# Easy_LED.net
KiCad netlist of a schematic drawn in EAGLE
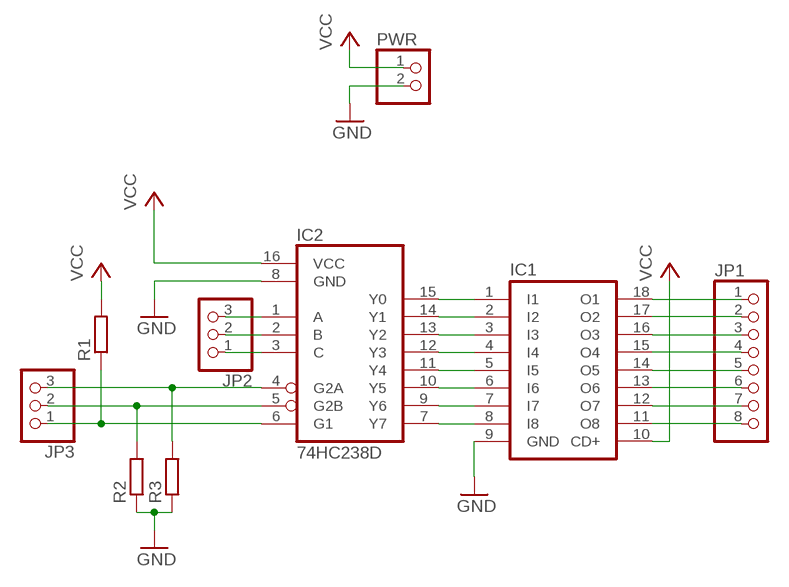
[diagram p0: schematic, sheet 1]

(export (version "E")
  (design (tool "Eeschema 10.0.6"))
  (components
    (comp (ref "IC1")
      (value "ULN2803ASOP18")
      (footprint "eagle-import:SOP18")
      (libsource (lib "eagle-import") (part "ULN2803ASOP18"))
    )
    (comp (ref "IC2")
      (value "74HC238D")
      (footprint "eagle-import:SO16")
      (libsource (lib "eagle-import") (part "74HC238D"))
    )
    (comp (ref "JP1")
      (value "PINHD-1X8")
      (footprint "eagle-import:1X08")
      (libsource (lib "eagle-import") (part "PINHD-1X8"))
    )
    (comp (ref "JP2")
      (value "PINHD-1X3")
      (footprint "eagle-import:1X03")
      (libsource (lib "eagle-import") (part "PINHD-1X3"))
    )
    (comp (ref "JP3")
      (value "PINHD-1X3")
      (footprint "eagle-import:1X03")
      (libsource (lib "eagle-import") (part "PINHD-1X3"))
    )
    (comp (ref "PWR")
      (value "PINHD-1X2")
      (footprint "eagle-import:1X02")
      (libsource (lib "eagle-import") (part "PINHD-1X2"))
    )
    (comp (ref "R1")
      (value "R-EU_0207/7")
      (footprint "eagle-import:0207_7")
      (libsource (lib "eagle-import") (part "R-EU_0207/7"))
    )
    (comp (ref "R2")
      (value "R-EU_M0805")
      (footprint "eagle-import:M0805")
      (libsource (lib "eagle-import") (part "R-EU_M0805"))
    )
    (comp (ref "R3")
      (value "R-EU_M0805")
      (footprint "eagle-import:M0805")
      (libsource (lib "eagle-import") (part "R-EU_M0805"))
    )
  )
  (nets
    (net (code "1") (name "GND") (class "Default")
      (node (ref "IC1") (pin "9") (pinfunction "GND_9") (pintype "power_in"))
      (node (ref "IC2") (pin "8") (pinfunction "GND_8") (pintype "power_in"))
      (node (ref "PWR") (pin "2") (pinfunction "2_2") (pintype "passive"))
      (node (ref "R2") (pin "1") (pinfunction "1_1") (pintype "passive"))
      (node (ref "R3") (pin "1") (pinfunction "1_1") (pintype "passive"))
    )
    (net (code "2") (name "Net-(IC1-I1)") (class "Default")
      (node (ref "IC1") (pin "1") (pinfunction "I1_1") (pintype "input"))
      (node (ref "IC2") (pin "15") (pinfunction "Y0_15") (pintype "output"))
    )
    (net (code "3") (name "Net-(IC1-I2)") (class "Default")
      (node (ref "IC1") (pin "2") (pinfunction "I2_2") (pintype "input"))
      (node (ref "IC2") (pin "14") (pinfunction "Y1_14") (pintype "output"))
    )
    (net (code "4") (name "Net-(IC1-I3)") (class "Default")
      (node (ref "IC1") (pin "3") (pinfunction "I3_3") (pintype "input"))
      (node (ref "IC2") (pin "13") (pinfunction "Y2_13") (pintype "output"))
    )
    (net (code "5") (name "Net-(IC1-I4)") (class "Default")
      (node (ref "IC1") (pin "4") (pinfunction "I4_4") (pintype "input"))
      (node (ref "IC2") (pin "12") (pinfunction "Y3_12") (pintype "output"))
    )
    (net (code "6") (name "Net-(IC1-I5)") (class "Default")
      (node (ref "IC1") (pin "5") (pinfunction "I5_5") (pintype "input"))
      (node (ref "IC2") (pin "11") (pinfunction "Y4_11") (pintype "output"))
    )
    (net (code "7") (name "Net-(IC1-I6)") (class "Default")
      (node (ref "IC1") (pin "6") (pinfunction "I6_6") (pintype "input"))
      (node (ref "IC2") (pin "10") (pinfunction "Y5_10") (pintype "output"))
    )
    (net (code "8") (name "Net-(IC1-I7)") (class "Default")
      (node (ref "IC1") (pin "7") (pinfunction "I7_7") (pintype "input"))
      (node (ref "IC2") (pin "9") (pinfunction "Y6_9") (pintype "output"))
    )
    (net (code "9") (name "Net-(IC1-I8)") (class "Default")
      (node (ref "IC1") (pin "8") (pinfunction "I8_8") (pintype "input"))
      (node (ref "IC2") (pin "7") (pinfunction "Y7_7") (pintype "output"))
    )
    (net (code "10") (name "Net-(IC1-O1)") (class "Default")
      (node (ref "IC1") (pin "18") (pinfunction "O1_18") (pintype "open_collector"))
      (node (ref "JP1") (pin "1") (pinfunction "1_1") (pintype "passive"))
    )
    (net (code "11") (name "Net-(IC1-O2)") (class "Default")
      (node (ref "IC1") (pin "17") (pinfunction "O2_17") (pintype "open_collector"))
      (node (ref "JP1") (pin "2") (pinfunction "2_2") (pintype "passive"))
    )
    (net (code "12") (name "Net-(IC1-O3)") (class "Default")
      (node (ref "IC1") (pin "16") (pinfunction "O3_16") (pintype "open_collector"))
      (node (ref "JP1") (pin "3") (pinfunction "3_3") (pintype "passive"))
    )
    (net (code "13") (name "Net-(IC1-O4)") (class "Default")
      (node (ref "IC1") (pin "15") (pinfunction "O4_15") (pintype "open_collector"))
      (node (ref "JP1") (pin "4") (pinfunction "4_4") (pintype "passive"))
    )
    (net (code "14") (name "Net-(IC1-O5)") (class "Default")
      (node (ref "IC1") (pin "14") (pinfunction "O5_14") (pintype "open_collector"))
      (node (ref "JP1") (pin "5") (pinfunction "5_5") (pintype "passive"))
    )
    (net (code "15") (name "Net-(IC1-O6)") (class "Default")
      (node (ref "IC1") (pin "13") (pinfunction "O6_13") (pintype "open_collector"))
      (node (ref "JP1") (pin "6") (pinfunction "6_6") (pintype "passive"))
    )
    (net (code "16") (name "Net-(IC1-O7)") (class "Default")
      (node (ref "IC1") (pin "12") (pinfunction "O7_12") (pintype "open_collector"))
      (node (ref "JP1") (pin "7") (pinfunction "7_7") (pintype "passive"))
    )
    (net (code "17") (name "Net-(IC1-O8)") (class "Default")
      (node (ref "IC1") (pin "11") (pinfunction "O8_11") (pintype "open_collector"))
      (node (ref "JP1") (pin "8") (pinfunction "8_8") (pintype "passive"))
    )
    (net (code "18") (name "Net-(IC2-A)") (class "Default")
      (node (ref "IC2") (pin "1") (pinfunction "A_1") (pintype "input"))
      (node (ref "JP2") (pin "3") (pinfunction "3_3") (pintype "passive"))
    )
    (net (code "19") (name "Net-(IC2-B)") (class "Default")
      (node (ref "IC2") (pin "2") (pinfunction "B_2") (pintype "input"))
      (node (ref "JP2") (pin "2") (pinfunction "2_2") (pintype "passive"))
    )
    (net (code "20") (name "Net-(IC2-C)") (class "Default")
      (node (ref "IC2") (pin "3") (pinfunction "C_3") (pintype "input"))
      (node (ref "JP2") (pin "1") (pinfunction "1_1") (pintype "passive"))
    )
    (net (code "21") (name "Net-(IC2-G1)") (class "Default")
      (node (ref "IC2") (pin "6") (pinfunction "G1_6") (pintype "input"))
      (node (ref "JP3") (pin "1") (pinfunction "1_1") (pintype "passive"))
      (node (ref "R1") (pin "1") (pinfunction "1_1") (pintype "passive"))
    )
    (net (code "22") (name "Net-(IC2-G2A)") (class "Default")
      (node (ref "IC2") (pin "4") (pinfunction "G2A_4") (pintype "input"))
      (node (ref "JP3") (pin "3") (pinfunction "3_3") (pintype "passive"))
      (node (ref "R3") (pin "2") (pinfunction "2_2") (pintype "passive"))
    )
    (net (code "23") (name "Net-(IC2-G2B)") (class "Default")
      (node (ref "IC2") (pin "5") (pinfunction "G2B_5") (pintype "input"))
      (node (ref "JP3") (pin "2") (pinfunction "2_2") (pintype "passive"))
      (node (ref "R2") (pin "2") (pinfunction "2_2") (pintype "passive"))
    )
    (net (code "24") (name "VCC") (class "Default")
      (node (ref "IC1") (pin "10") (pinfunction "CD+_10") (pintype "passive"))
      (node (ref "IC2") (pin "16") (pinfunction "VCC_16") (pintype "power_in"))
      (node (ref "PWR") (pin "1") (pinfunction "1_1") (pintype "passive"))
      (node (ref "R1") (pin "2") (pinfunction "2_2") (pintype "passive"))
    )
  )
)
